# Ethernet.net
KiCad netlist of a schematic drawn in Altium Designer
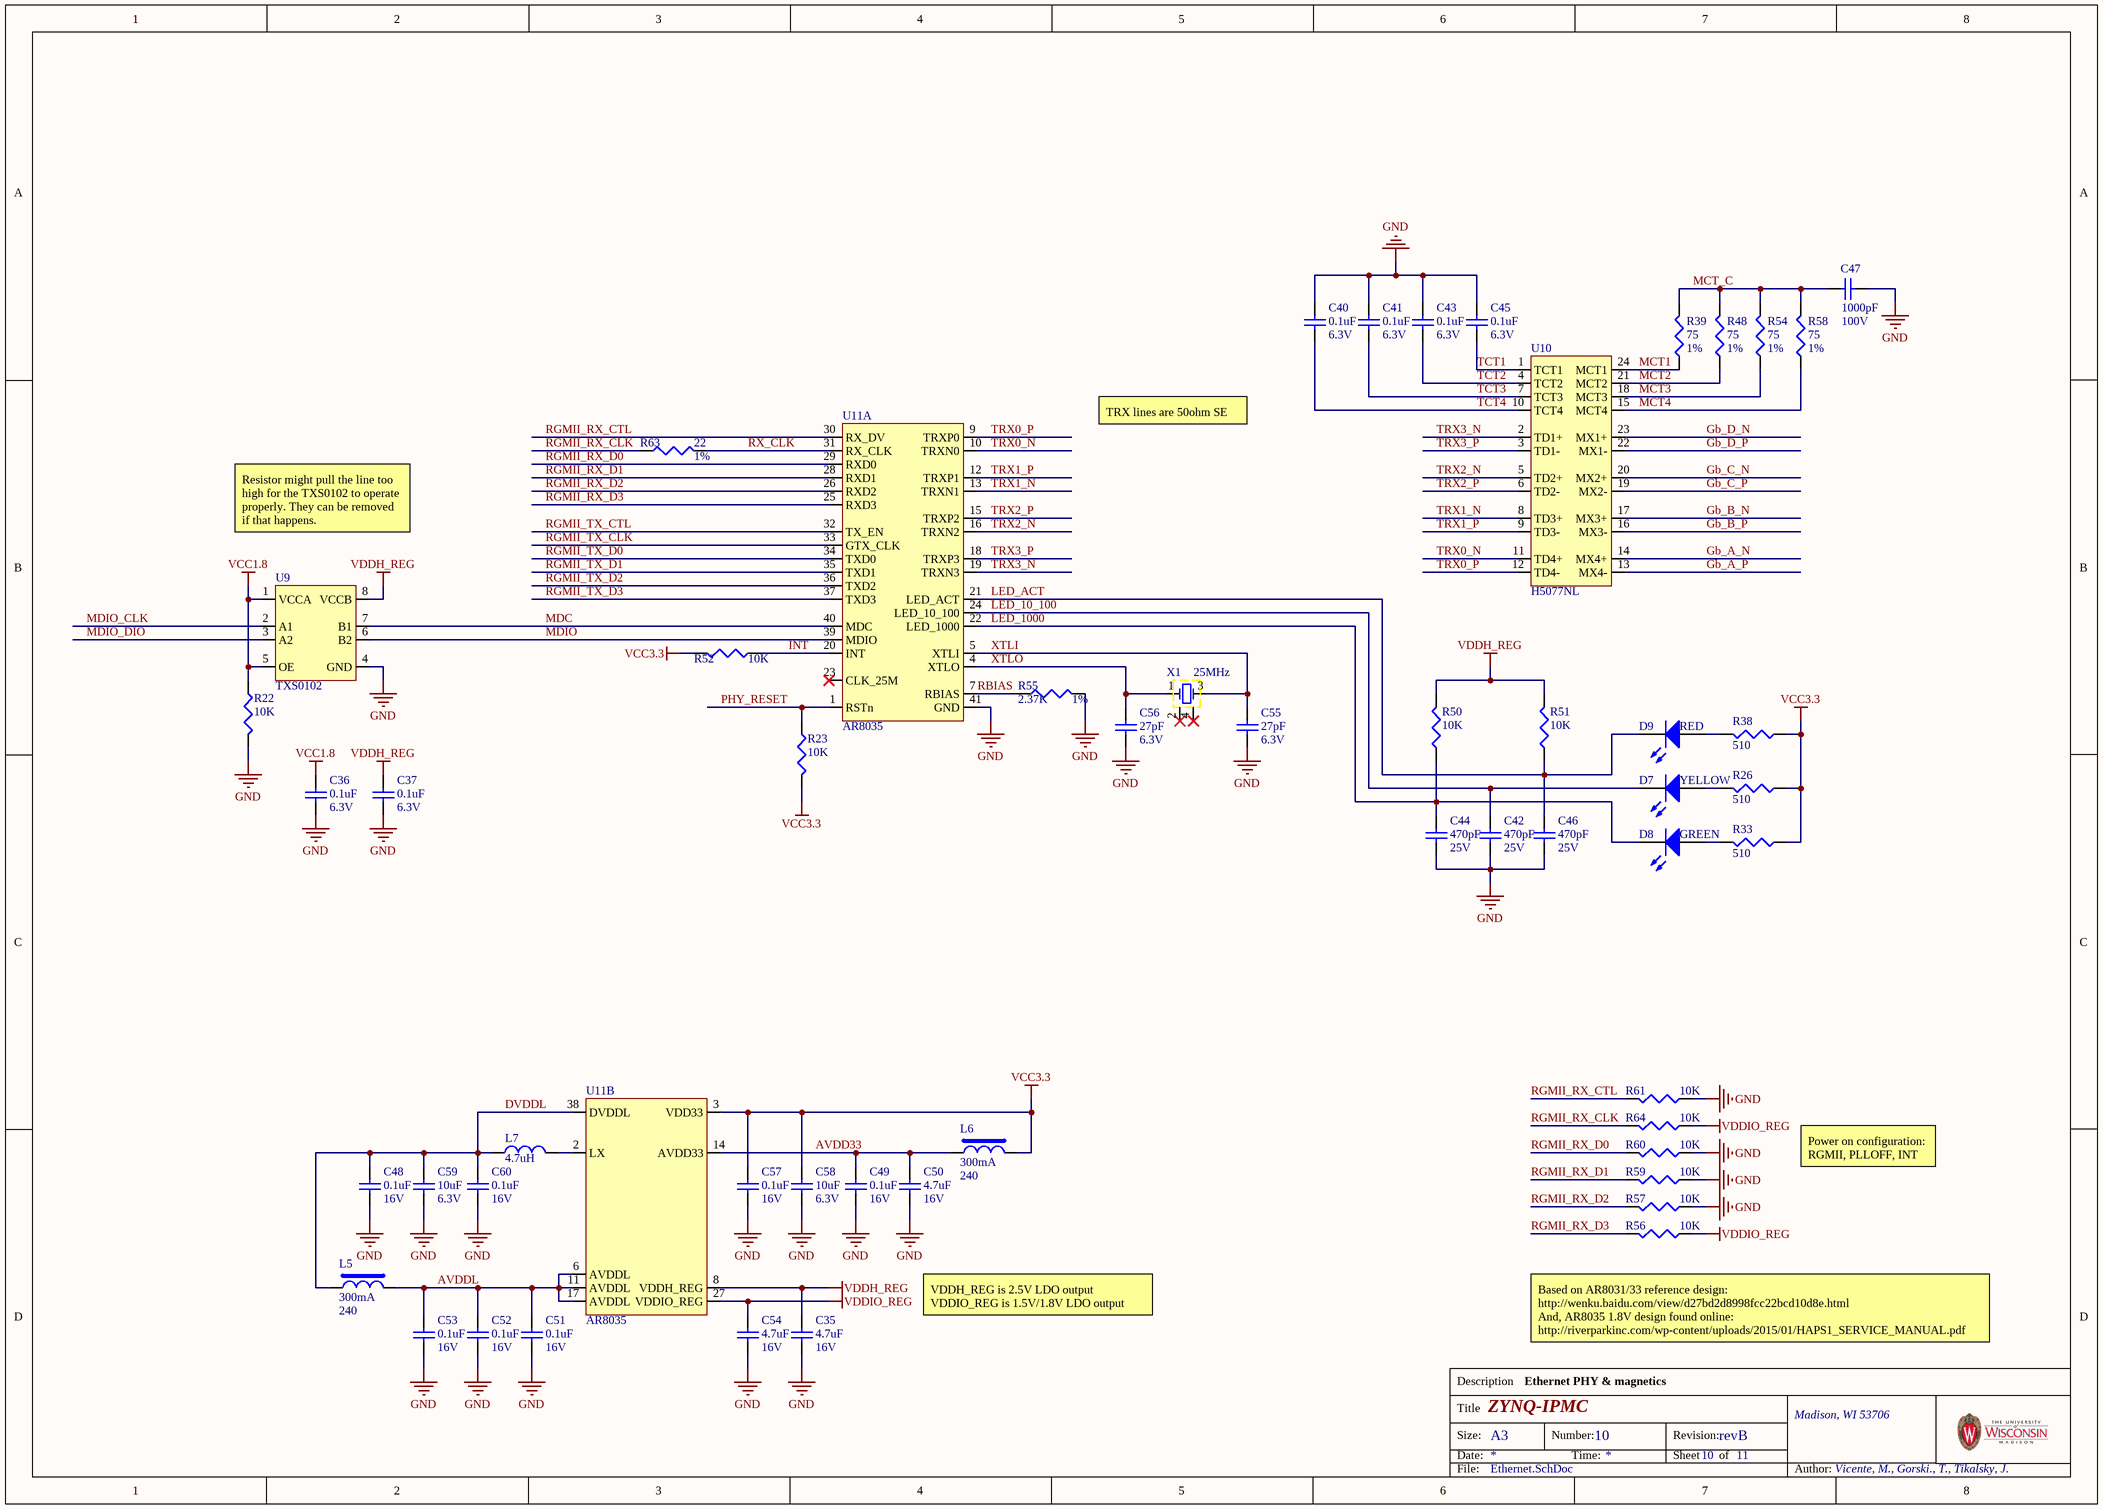
[diagram p0: Ethernet.SchDoc]

(export (version "E")
  (design (tool "Eeschema 10.0.6"))
  (components
    (comp (ref "C35")
      (value "4.7uF")
      (footprint "C0402_IPC_H")
      (description "Capacitor")
      (fields
        (field (name "RATING") "16V")
        (field (name "MANUFACTURER") "AVX")
        (field (name "PART") "0402YD475MAT2A")
      )
      (libsource (lib "CustomParts") (part "Cap"))
    )
    (comp (ref "C36")
      (value "0.1uF")
      (footprint "C0201_IPC_H")
      (description "Capacitor")
      (fields
        (field (name "RATING") "6.3V")
        (field (name "MANUFACTURER") "Murata")
        (field (name "PART") "GRM033R60J104KE19D")
      )
      (libsource (lib "CustomParts") (part "Cap"))
    )
    (comp (ref "C37")
      (value "0.1uF")
      (footprint "C0201_IPC_H")
      (description "Capacitor")
      (fields
        (field (name "RATING") "6.3V")
        (field (name "MANUFACTURER") "Murata")
        (field (name "PART") "GRM033R60J104KE19D")
      )
      (libsource (lib "CustomParts") (part "Cap"))
    )
    (comp (ref "C40")
      (value "0.1uF")
      (footprint "C0201_IPC_H")
      (description "Capacitor")
      (fields
        (field (name "RATING") "6.3V")
        (field (name "MANUFACTURER") "Murata")
        (field (name "PART") "GRM033R60J104KE19D")
      )
      (libsource (lib "CustomParts") (part "Cap"))
    )
    (comp (ref "C41")
      (value "0.1uF")
      (footprint "C0201_IPC_H")
      (description "Capacitor")
      (fields
        (field (name "RATING") "6.3V")
        (field (name "MANUFACTURER") "Murata")
        (field (name "PART") "GRM033R60J104KE19D")
      )
      (libsource (lib "CustomParts") (part "Cap"))
    )
    (comp (ref "C42")
      (value "470pF")
      (footprint "C0201_IPC_H")
      (description "Capacitor")
      (fields
        (field (name "RATING") "25V")
        (field (name "MANUFACTURER") "TDK")
        (field (name "PART") "C0603X7R1E471K030BA")
      )
      (libsource (lib "CustomParts") (part "Cap"))
    )
    (comp (ref "C43")
      (value "0.1uF")
      (footprint "C0201_IPC_H")
      (description "Capacitor")
      (fields
        (field (name "RATING") "6.3V")
        (field (name "MANUFACTURER") "Murata")
        (field (name "PART") "GRM033R60J104KE19D")
      )
      (libsource (lib "CustomParts") (part "Cap"))
    )
    (comp (ref "C44")
      (value "470pF")
      (footprint "C0201_IPC_H")
      (description "Capacitor")
      (fields
        (field (name "RATING") "25V")
        (field (name "MANUFACTURER") "TDK")
        (field (name "PART") "C0603X7R1E471K030BA")
      )
      (libsource (lib "CustomParts") (part "Cap"))
    )
    (comp (ref "C45")
      (value "0.1uF")
      (footprint "C0201_IPC_H")
      (description "Capacitor")
      (fields
        (field (name "RATING") "6.3V")
        (field (name "MANUFACTURER") "Murata")
        (field (name "PART") "GRM033R60J104KE19D")
      )
      (libsource (lib "CustomParts") (part "Cap"))
    )
    (comp (ref "C46")
      (value "470pF")
      (footprint "C0201_IPC_H")
      (description "Capacitor")
      (fields
        (field (name "RATING") "25V")
        (field (name "MANUFACTURER") "TDK")
        (field (name "PART") "C0603X7R1E471K030BA")
      )
      (libsource (lib "CustomParts") (part "Cap"))
    )
    (comp (ref "C47")
      (value "1000pF")
      (footprint "C0402_IPC_H")
      (description "Capacitor")
      (fields
        (field (name "RATING") "100V")
        (field (name "MANUFACTURER") "Murata")
        (field (name "PART") "GRM155R72A102KA01D")
      )
      (libsource (lib "CustomParts") (part "Cap"))
    )
    (comp (ref "C48")
      (value "0.1uF")
      (footprint "C0402_IPC_H")
      (description "Capacitor")
      (fields
        (field (name "RATING") "16V")
        (field (name "MANUFACTURER") "Murata")
        (field (name "PART") "GRM155R71C104KA88D")
      )
      (libsource (lib "CustomParts") (part "Cap"))
    )
    (comp (ref "C49")
      (value "0.1uF")
      (footprint "C0402_IPC_H")
      (description "Capacitor")
      (fields
        (field (name "RATING") "16V")
        (field (name "MANUFACTURER") "Murata")
        (field (name "PART") "GRM155R71C104KA88D")
      )
      (libsource (lib "CustomParts") (part "Cap"))
    )
    (comp (ref "C50")
      (value "4.7uF")
      (footprint "C0402_IPC_H")
      (description "Capacitor")
      (fields
        (field (name "RATING") "16V")
        (field (name "MANUFACTURER") "AVX")
        (field (name "PART") "0402YD475MAT2A")
      )
      (libsource (lib "CustomParts") (part "Cap"))
    )
    (comp (ref "C51")
      (value "0.1uF")
      (footprint "C0402_IPC_H")
      (description "Capacitor")
      (fields
        (field (name "RATING") "16V")
        (field (name "MANUFACTURER") "Murata")
        (field (name "PART") "GRM155R71C104KA88D")
      )
      (libsource (lib "CustomParts") (part "Cap"))
    )
    (comp (ref "C52")
      (value "0.1uF")
      (footprint "C0402_IPC_H")
      (description "Capacitor")
      (fields
        (field (name "RATING") "16V")
        (field (name "MANUFACTURER") "Murata")
        (field (name "PART") "GRM155R71C104KA88D")
      )
      (libsource (lib "CustomParts") (part "Cap"))
    )
    (comp (ref "C53")
      (value "0.1uF")
      (footprint "C0402_IPC_H")
      (description "Capacitor")
      (fields
        (field (name "RATING") "16V")
        (field (name "MANUFACTURER") "Murata")
        (field (name "PART") "GRM155R71C104KA88D")
      )
      (libsource (lib "CustomParts") (part "Cap"))
    )
    (comp (ref "C54")
      (value "4.7uF")
      (footprint "C0402_IPC_H")
      (description "Capacitor")
      (fields
        (field (name "RATING") "16V")
        (field (name "MANUFACTURER") "AVX")
        (field (name "PART") "0402YD475MAT2A")
      )
      (libsource (lib "CustomParts") (part "Cap"))
    )
    (comp (ref "C55")
      (value "27pF")
      (footprint "C0201_IPC_H")
      (description "Capacitor")
      (fields
        (field (name "RATING") "6.3V")
        (field (name "MANUFACTURER") "Murata")
        (field (name "PART") "GJM0335C0J270JB01D")
      )
      (libsource (lib "CustomParts") (part "Cap"))
    )
    (comp (ref "C56")
      (value "27pF")
      (footprint "C0201_IPC_H")
      (description "Capacitor")
      (fields
        (field (name "RATING") "6.3V")
        (field (name "MANUFACTURER") "Murata")
        (field (name "PART") "GJM0335C0J270JB01D")
      )
      (libsource (lib "CustomParts") (part "Cap"))
    )
    (comp (ref "C57")
      (value "0.1uF")
      (footprint "C0402_IPC_H")
      (description "Capacitor")
      (fields
        (field (name "RATING") "16V")
        (field (name "MANUFACTURER") "Murata")
        (field (name "PART") "GRM155R71C104KA88D")
      )
      (libsource (lib "CustomParts") (part "Cap"))
    )
    (comp (ref "C58")
      (value "10uF")
      (footprint "C0402_IPC_H")
      (description "Capacitor")
      (fields
        (field (name "RATING") "6.3V")
        (field (name "MANUFACTURER") "Murata")
        (field (name "PART") "GRM155R60J106ME44D")
      )
      (libsource (lib "CustomParts") (part "Cap"))
    )
    (comp (ref "C59")
      (value "10uF")
      (footprint "C0402_IPC_H")
      (description "Capacitor")
      (fields
        (field (name "RATING") "6.3V")
        (field (name "MANUFACTURER") "Murata")
        (field (name "PART") "GRM155R60J106ME44D")
      )
      (libsource (lib "CustomParts") (part "Cap"))
    )
    (comp (ref "C60")
      (value "0.1uF")
      (footprint "C0402_IPC_H")
      (description "Capacitor")
      (fields
        (field (name "RATING") "16V")
        (field (name "MANUFACTURER") "Murata")
        (field (name "PART") "GRM155R71C104KA88D")
      )
      (libsource (lib "CustomParts") (part "Cap"))
    )
    (comp (ref "D7")
      (value "YELLOW")
      (footprint "LED0603_M")
      (description "Light Emitting Diode")
      (fields (field (name "MANUFACTURER") "Lite-On") (field (name "PART") "LTST-C190KSKT"))
      (libsource (lib "CustomParts") (part "LED"))
    )
    (comp (ref "D8")
      (value "GREEN")
      (footprint "LED0603_M")
      (description "Light Emitting Diode")
      (fields (field (name "MANUFACTURER") "Lite-On") (field (name "PART") "LTST-C190KGKT"))
      (libsource (lib "CustomParts") (part "LED"))
    )
    (comp (ref "D9")
      (value "RED")
      (footprint "LED0603_M")
      (description "Light Emitting Diode")
      (fields (field (name "MANUFACTURER") "Lite-On") (field (name "PART") "LTST-C190KRKT"))
      (libsource (lib "CustomParts") (part "LED"))
    )
    (comp (ref "L5")
      (value "240")
      (footprint "L0402_H")
      (description "Bead Inductor")
      (fields
        (field (name "RATED CURRENT") "300mA")
        (field (name "MANUFACTURER") "Taiyo Yuden")
        (field (name "PART") "BK1005HM241-T")
      )
      (libsource (lib "CustomParts") (part "Bead"))
    )
    (comp (ref "L6")
      (value "240")
      (footprint "L0402_H")
      (description "Bead Inductor")
      (fields
        (field (name "RATED CURRENT") "300mA")
        (field (name "MANUFACTURER") "Taiyo Yuden")
        (field (name "PART") "BK1005HM241-T")
      )
      (libsource (lib "CustomParts") (part "Bead"))
    )
    (comp (ref "L7")
      (value "4.7uH")
      (footprint "L2520_H")
      (description "Inductor")
      (fields (field (name "TOLERANCE") "20%") (field (name "MANUFACTURER") "Wurth"))
      (libsource (lib "CustomParts") (part "Ind"))
    )
    (comp (ref "R22")
      (value "10K")
      (footprint "R0402_IPC_H")
      (description "Resistor")
      (fields (field (name "TOLERANCE") "5%") (field (name "MANUFACTURER") "Panasonic-ECG"))
      (libsource (lib "CustomParts") (part "Res"))
    )
    (comp (ref "R23")
      (value "10K")
      (footprint "R0201_IPC_H")
      (description "Resistor")
      (fields (field (name "TOLERANCE") "1%") (field (name "MANUFACTURER") "Panasonic"))
      (libsource (lib "CustomParts") (part "Res"))
    )
    (comp (ref "R26")
      (value "510")
      (footprint "R0402_IPC_H")
      (description "Resistor")
      (fields (field (name "TOLERANCE") "1%") (field (name "MANUFACTURER") "Panasonic-ECG"))
      (libsource (lib "CustomParts") (part "Res"))
    )
    (comp (ref "R33")
      (value "510")
      (footprint "R0402_IPC_H")
      (description "Resistor")
      (fields (field (name "TOLERANCE") "1%") (field (name "MANUFACTURER") "Panasonic-ECG"))
      (libsource (lib "CustomParts") (part "Res"))
    )
    (comp (ref "R38")
      (value "510")
      (footprint "R0402_IPC_H")
      (description "Resistor")
      (fields (field (name "TOLERANCE") "1%") (field (name "MANUFACTURER") "Panasonic-ECG"))
      (libsource (lib "CustomParts") (part "Res"))
    )
    (comp (ref "R39")
      (value "75")
      (footprint "R0402_IPC_H")
      (description "Resistor")
      (fields
        (field (name "TOLERANCE") "1%")
        (field (name "MANUFACTURER") "Panasonic")
        (field (name "PART") "ERJ-2RKF75R0X")
      )
      (libsource (lib "CustomParts") (part "Res"))
    )
    (comp (ref "R48")
      (value "75")
      (footprint "R0402_IPC_H")
      (description "Resistor")
      (fields
        (field (name "TOLERANCE") "1%")
        (field (name "MANUFACTURER") "Panasonic")
        (field (name "PART") "ERJ-2RKF75R0X")
      )
      (libsource (lib "CustomParts") (part "Res"))
    )
    (comp (ref "R50")
      (value "10K")
      (footprint "R0201_IPC_H")
      (description "Resistor")
      (fields (field (name "TOLERANCE") "1%") (field (name "MANUFACTURER") "Panasonic"))
      (libsource (lib "CustomParts") (part "Res"))
    )
    (comp (ref "R51")
      (value "10K")
      (footprint "R0201_IPC_H")
      (description "Resistor")
      (fields (field (name "TOLERANCE") "1%") (field (name "MANUFACTURER") "Panasonic"))
      (libsource (lib "CustomParts") (part "Res"))
    )
    (comp (ref "R52")
      (value "10K")
      (footprint "R0402_IPC_H")
      (description "Resistor")
      (fields (field (name "TOLERANCE") "5%") (field (name "MANUFACTURER") "Panasonic-ECG"))
      (libsource (lib "CustomParts") (part "Res"))
    )
    (comp (ref "R54")
      (value "75")
      (footprint "R0402_IPC_H")
      (description "Resistor")
      (fields
        (field (name "TOLERANCE") "1%")
        (field (name "MANUFACTURER") "Panasonic")
        (field (name "PART") "ERJ-2RKF75R0X")
      )
      (libsource (lib "CustomParts") (part "Res"))
    )
    (comp (ref "R55")
      (value "2.37K")
      (footprint "R0402_IPC_H")
      (description "Resistor")
      (fields
        (field (name "TOLERANCE") "1%")
        (field (name "MANUFACTURER") "Panasonic")
        (field (name "PART") "ERJ-2RKF2371X")
      )
      (libsource (lib "CustomParts") (part "Res"))
    )
    (comp (ref "R56")
      (value "10K")
      (footprint "R0402_IPC_H")
      (description "Resistor")
      (fields (field (name "TOLERANCE") "5%") (field (name "MANUFACTURER") "Panasonic-ECG"))
      (libsource (lib "CustomParts") (part "Res"))
    )
    (comp (ref "R57")
      (value "10K")
      (footprint "R0402_IPC_H")
      (description "Resistor")
      (fields (field (name "TOLERANCE") "5%") (field (name "MANUFACTURER") "Panasonic-ECG"))
      (libsource (lib "CustomParts") (part "Res"))
    )
    (comp (ref "R58")
      (value "75")
      (footprint "R0402_IPC_H")
      (description "Resistor")
      (fields
        (field (name "TOLERANCE") "1%")
        (field (name "MANUFACTURER") "Panasonic")
        (field (name "PART") "ERJ-2RKF75R0X")
      )
      (libsource (lib "CustomParts") (part "Res"))
    )
    (comp (ref "R59")
      (value "10K")
      (footprint "R0402_IPC_H")
      (description "Resistor")
      (fields (field (name "TOLERANCE") "5%") (field (name "MANUFACTURER") "Panasonic-ECG"))
      (libsource (lib "CustomParts") (part "Res"))
    )
    (comp (ref "R60")
      (value "10K")
      (footprint "R0402_IPC_H")
      (description "Resistor")
      (fields (field (name "TOLERANCE") "5%") (field (name "MANUFACTURER") "Panasonic-ECG"))
      (libsource (lib "CustomParts") (part "Res"))
    )
    (comp (ref "R61")
      (value "10K")
      (footprint "R0402_IPC_H")
      (description "Resistor")
      (fields (field (name "TOLERANCE") "5%") (field (name "MANUFACTURER") "Panasonic-ECG"))
      (libsource (lib "CustomParts") (part "Res"))
    )
    (comp (ref "R63")
      (value "22")
      (footprint "R0201_IPC_H")
      (description "Resistor")
      (fields
        (field (name "TOLERANCE") "1%")
        (field (name "MANUFACTURER") "Panasonic")
        (field (name "PART") "ERJ-1GNF22R0C")
      )
      (libsource (lib "CustomParts") (part "Res"))
    )
    (comp (ref "R64")
      (value "10K")
      (footprint "R0402_IPC_H")
      (description "Resistor")
      (fields (field (name "TOLERANCE") "5%") (field (name "MANUFACTURER") "Panasonic-ECG"))
      (libsource (lib "CustomParts") (part "Res"))
    )
    (comp (ref "U9")
      (value "TXS0102")
      (footprint "X2SON-8_H")
      (description "2-Bit Bidirectional Voltage-Level Translator for Open-Drain and Push-Pull Applications")
      (fields (field (name "MANUFACTURER") "Texas Instruments") (field (name "PART") "TXS0102DQER"))
      (libsource (lib "CustomParts") (part "TXS0102"))
    )
    (comp (ref "U10")
      (value "H5077NL")
      (footprint "H5077NL")
      (description "1000Base-T, Single Port Mini-Magnetics Modules")
      (fields (field (name "MANUFACTURER") "Pulse Electronics"))
      (libsource (lib "CustomParts") (part "H5077NL"))
    )
    (comp (ref "U11")
      (value "AR8035")
      (footprint "QFN40_H")
      (description "Integrated 10/100/1000 Gigabit Ethernet Transceiver")
      (fields (field (name "MANUFACTURER") "Atheros"))
      (libsource (lib "CustomParts") (part "AR8035"))
    )
    (comp (ref "X1")
      (value "25MHz")
      (footprint "XRCGB_F")
      (description "Standard Crystal Oscillator")
      (fields (field (name "MANUFACTURER") "Murata") (field (name "PART") "XRCGB25M000F3M00R0"))
      (libsource (lib "CustomParts") (part "Crystal Osc"))
    )
  )
  (nets
    (net (code "1") (name "/AVDD33") (class "Default")
      (node (ref "C49") (pin "2") (pinfunction "2_2") (pintype "passive"))
      (node (ref "C50") (pin "2") (pinfunction "2_2") (pintype "passive"))
      (node (ref "L6") (pin "1") (pinfunction "1_1") (pintype "passive"))
      (node (ref "U11") (pin "14") (pinfunction "AVDD33_14") (pintype "passive"))
    )
    (net (code "2") (name "/AVDDL") (class "Default")
      (node (ref "C51") (pin "2") (pinfunction "2_2") (pintype "passive"))
      (node (ref "C52") (pin "2") (pinfunction "2_2") (pintype "passive"))
      (node (ref "C53") (pin "2") (pinfunction "2_2") (pintype "passive"))
      (node (ref "L5") (pin "2") (pinfunction "2_2") (pintype "passive"))
      (node (ref "U11") (pin "11") (pinfunction "AVDDL_11") (pintype "passive"))
      (node (ref "U11") (pin "17") (pinfunction "AVDDL_17") (pintype "passive"))
      (node (ref "U11") (pin "6") (pinfunction "AVDDL_6") (pintype "passive"))
    )
    (net (code "3") (name "/DVDDL") (class "Default")
      (node (ref "C48") (pin "2") (pinfunction "2_2") (pintype "passive"))
      (node (ref "C59") (pin "2") (pinfunction "2_2") (pintype "passive"))
      (node (ref "C60") (pin "2") (pinfunction "2_2") (pintype "passive"))
      (node (ref "L5") (pin "1") (pinfunction "1_1") (pintype "passive"))
      (node (ref "L7") (pin "1") (pinfunction "1_1") (pintype "passive"))
      (node (ref "U11") (pin "38") (pinfunction "DVDDL_38") (pintype "passive"))
    )
    (net (code "4") (name "/Gb_A_N") (class "Default")
      (node (ref "U10") (pin "14") (pinfunction "MX4+_14") (pintype "passive"))
    )
    (net (code "5") (name "/Gb_A_P") (class "Default")
      (node (ref "U10") (pin "13") (pinfunction "MX4-_13") (pintype "passive"))
    )
    (net (code "6") (name "/Gb_B_N") (class "Default")
      (node (ref "U10") (pin "17") (pinfunction "MX3+_17") (pintype "passive"))
    )
    (net (code "7") (name "/Gb_B_P") (class "Default")
      (node (ref "U10") (pin "16") (pinfunction "MX3-_16") (pintype "passive"))
    )
    (net (code "8") (name "/Gb_C_N") (class "Default")
      (node (ref "U10") (pin "20") (pinfunction "MX2+_20") (pintype "passive"))
    )
    (net (code "9") (name "/Gb_C_P") (class "Default")
      (node (ref "U10") (pin "19") (pinfunction "MX2-_19") (pintype "passive"))
    )
    (net (code "10") (name "/Gb_D_N") (class "Default")
      (node (ref "U10") (pin "23") (pinfunction "MX1+_23") (pintype "passive"))
    )
    (net (code "11") (name "/Gb_D_P") (class "Default")
      (node (ref "U10") (pin "22") (pinfunction "MX1-_22") (pintype "passive"))
    )
    (net (code "12") (name "/INT") (class "Default")
      (node (ref "R52") (pin "1") (pinfunction "1_1") (pintype "passive"))
      (node (ref "U11") (pin "20") (pinfunction "INT_20") (pintype "passive"))
    )
    (net (code "13") (name "/LED_10_100") (class "Default")
      (node (ref "C42") (pin "2") (pinfunction "2_2") (pintype "passive"))
      (node (ref "D7") (pin "2") (pinfunction "K_2") (pintype "passive"))
      (node (ref "U11") (pin "24") (pinfunction "LED_10_100_24") (pintype "passive"))
    )
    (net (code "14") (name "/LED_1000") (class "Default")
      (node (ref "C44") (pin "2") (pinfunction "2_2") (pintype "passive"))
      (node (ref "D8") (pin "2") (pinfunction "K_2") (pintype "passive"))
      (node (ref "R50") (pin "1") (pinfunction "1_1") (pintype "passive"))
      (node (ref "U11") (pin "22") (pinfunction "LED_1000_22") (pintype "passive"))
    )
    (net (code "15") (name "/LED_ACT") (class "Default")
      (node (ref "C46") (pin "2") (pinfunction "2_2") (pintype "passive"))
      (node (ref "D9") (pin "2") (pinfunction "K_2") (pintype "passive"))
      (node (ref "R51") (pin "1") (pinfunction "1_1") (pintype "passive"))
      (node (ref "U11") (pin "21") (pinfunction "LED_ACT_21") (pintype "passive"))
    )
    (net (code "16") (name "/MCT1") (class "Default")
      (node (ref "R39") (pin "1") (pinfunction "1_1") (pintype "passive"))
      (node (ref "U10") (pin "24") (pinfunction "MCT1_24") (pintype "passive"))
    )
    (net (code "17") (name "/MCT2") (class "Default")
      (node (ref "R48") (pin "1") (pinfunction "1_1") (pintype "passive"))
      (node (ref "U10") (pin "21") (pinfunction "MCT2_21") (pintype "passive"))
    )
    (net (code "18") (name "/MCT3") (class "Default")
      (node (ref "R54") (pin "1") (pinfunction "1_1") (pintype "passive"))
      (node (ref "U10") (pin "18") (pinfunction "MCT3_18") (pintype "passive"))
    )
    (net (code "19") (name "/MCT4") (class "Default")
      (node (ref "R58") (pin "1") (pinfunction "1_1") (pintype "passive"))
      (node (ref "U10") (pin "15") (pinfunction "MCT4_15") (pintype "passive"))
    )
    (net (code "20") (name "/MCT_C") (class "Default")
      (node (ref "C47") (pin "2") (pinfunction "2_2") (pintype "passive"))
      (node (ref "R39") (pin "2") (pinfunction "2_2") (pintype "passive"))
      (node (ref "R48") (pin "2") (pinfunction "2_2") (pintype "passive"))
      (node (ref "R54") (pin "2") (pinfunction "2_2") (pintype "passive"))
      (node (ref "R58") (pin "2") (pinfunction "2_2") (pintype "passive"))
    )
    (net (code "21") (name "/MDC") (class "Default")
      (node (ref "U11") (pin "40") (pinfunction "MDC_40") (pintype "passive"))
      (node (ref "U9") (pin "7") (pinfunction "B1_7") (pintype "passive"))
    )
    (net (code "22") (name "/MDIO") (class "Default")
      (node (ref "U11") (pin "39") (pinfunction "MDIO_39") (pintype "passive"))
      (node (ref "U9") (pin "6") (pinfunction "B2_6") (pintype "passive"))
    )
    (net (code "23") (name "/MDIO_CLK") (class "Default")
      (node (ref "U9") (pin "2") (pinfunction "A1_2") (pintype "passive"))
    )
    (net (code "24") (name "/MDIO_DIO") (class "Default")
      (node (ref "U9") (pin "3") (pinfunction "A2_3") (pintype "passive"))
    )
    (net (code "25") (name "/PHY_RESET") (class "Default")
      (node (ref "R23") (pin "1") (pinfunction "1_1") (pintype "passive"))
      (node (ref "U11") (pin "1") (pinfunction "RSTn_1") (pintype "passive"))
    )
    (net (code "26") (name "/RBIAS") (class "Default")
      (node (ref "R55") (pin "1") (pinfunction "1_1") (pintype "passive"))
      (node (ref "U11") (pin "7") (pinfunction "RBIAS_7") (pintype "passive"))
    )
    (net (code "27") (name "/RGMII_RX_CLK") (class "Default")
      (node (ref "R63") (pin "1") (pinfunction "1_1") (pintype "passive"))
      (node (ref "R64") (pin "2") (pinfunction "2_2") (pintype "passive"))
    )
    (net (code "28") (name "/RGMII_RX_CTL") (class "Default")
      (node (ref "R61") (pin "2") (pinfunction "2_2") (pintype "passive"))
      (node (ref "U11") (pin "30") (pinfunction "RX_DV_30") (pintype "passive"))
    )
    (net (code "29") (name "/RGMII_RX_D0") (class "Default")
      (node (ref "R60") (pin "2") (pinfunction "2_2") (pintype "passive"))
      (node (ref "U11") (pin "29") (pinfunction "RXD0_29") (pintype "passive"))
    )
    (net (code "30") (name "/RGMII_RX_D1") (class "Default")
      (node (ref "R59") (pin "2") (pinfunction "2_2") (pintype "passive"))
      (node (ref "U11") (pin "28") (pinfunction "RXD1_28") (pintype "passive"))
    )
    (net (code "31") (name "/RGMII_RX_D2") (class "Default")
      (node (ref "R57") (pin "2") (pinfunction "2_2") (pintype "passive"))
      (node (ref "U11") (pin "26") (pinfunction "RXD2_26") (pintype "passive"))
    )
    (net (code "32") (name "/RGMII_RX_D3") (class "Default")
      (node (ref "R56") (pin "2") (pinfunction "2_2") (pintype "passive"))
      (node (ref "U11") (pin "25") (pinfunction "RXD3_25") (pintype "passive"))
    )
    (net (code "33") (name "/RGMII_TX_CLK") (class "Default")
      (node (ref "U11") (pin "33") (pinfunction "GTX_CLK_33") (pintype "passive"))
    )
    (net (code "34") (name "/RGMII_TX_CTL") (class "Default")
      (node (ref "U11") (pin "32") (pinfunction "TX_EN_32") (pintype "passive"))
    )
    (net (code "35") (name "/RGMII_TX_D0") (class "Default")
      (node (ref "U11") (pin "34") (pinfunction "TXD0_34") (pintype "passive"))
    )
    (net (code "36") (name "/RGMII_TX_D1") (class "Default")
      (node (ref "U11") (pin "35") (pinfunction "TXD1_35") (pintype "passive"))
    )
    (net (code "37") (name "/RGMII_TX_D2") (class "Default")
      (node (ref "U11") (pin "36") (pinfunction "TXD2_36") (pintype "passive"))
    )
    (net (code "38") (name "/RGMII_TX_D3") (class "Default")
      (node (ref "U11") (pin "37") (pinfunction "TXD3_37") (pintype "passive"))
    )
    (net (code "39") (name "/RX_CLK") (class "Default")
      (node (ref "R63") (pin "2") (pinfunction "2_2") (pintype "passive"))
      (node (ref "U11") (pin "31") (pinfunction "RX_CLK_31") (pintype "passive"))
    )
    (net (code "40") (name "/TCT1") (class "Default")
      (node (ref "C45") (pin "1") (pinfunction "1_1") (pintype "passive"))
      (node (ref "U10") (pin "1") (pinfunction "TCT1_1") (pintype "passive"))
    )
    (net (code "41") (name "/TCT2") (class "Default")
      (node (ref "C43") (pin "1") (pinfunction "1_1") (pintype "passive"))
      (node (ref "U10") (pin "4") (pinfunction "TCT2_4") (pintype "passive"))
    )
    (net (code "42") (name "/TCT3") (class "Default")
      (node (ref "C41") (pin "1") (pinfunction "1_1") (pintype "passive"))
      (node (ref "U10") (pin "7") (pinfunction "TCT3_7") (pintype "passive"))
    )
    (net (code "43") (name "/TCT4") (class "Default")
      (node (ref "C40") (pin "1") (pinfunction "1_1") (pintype "passive"))
      (node (ref "U10") (pin "10") (pinfunction "TCT4_10") (pintype "passive"))
    )
    (net (code "44") (name "/TRX0_N") (class "Default")
      (node (ref "U10") (pin "11") (pinfunction "TD4+_11") (pintype "passive"))
      (node (ref "U11") (pin "10") (pinfunction "TRXN0_10") (pintype "passive"))
    )
    (net (code "45") (name "/TRX0_P") (class "Default")
      (node (ref "U10") (pin "12") (pinfunction "TD4-_12") (pintype "passive"))
      (node (ref "U11") (pin "9") (pinfunction "TRXP0_9") (pintype "passive"))
    )
    (net (code "46") (name "/TRX1_N") (class "Default")
      (node (ref "U10") (pin "8") (pinfunction "TD3+_8") (pintype "passive"))
      (node (ref "U11") (pin "13") (pinfunction "TRXN1_13") (pintype "passive"))
    )
    (net (code "47") (name "/TRX1_P") (class "Default")
      (node (ref "U10") (pin "9") (pinfunction "TD3-_9") (pintype "passive"))
      (node (ref "U11") (pin "12") (pinfunction "TRXP1_12") (pintype "passive"))
    )
    (net (code "48") (name "/TRX2_N") (class "Default")
      (node (ref "U10") (pin "5") (pinfunction "TD2+_5") (pintype "passive"))
      (node (ref "U11") (pin "16") (pinfunction "TRXN2_16") (pintype "passive"))
    )
    (net (code "49") (name "/TRX2_P") (class "Default")
      (node (ref "U10") (pin "6") (pinfunction "TD2-_6") (pintype "passive"))
      (node (ref "U11") (pin "15") (pinfunction "TRXP2_15") (pintype "passive"))
    )
    (net (code "50") (name "/TRX3_N") (class "Default")
      (node (ref "U10") (pin "2") (pinfunction "TD1+_2") (pintype "passive"))
      (node (ref "U11") (pin "19") (pinfunction "TRXN3_19") (pintype "passive"))
    )
    (net (code "51") (name "/TRX3_P") (class "Default")
      (node (ref "U10") (pin "3") (pinfunction "TD1-_3") (pintype "passive"))
      (node (ref "U11") (pin "18") (pinfunction "TRXP3_18") (pintype "passive"))
    )
    (net (code "52") (name "/XTLI") (class "Default")
      (node (ref "C55") (pin "2") (pinfunction "2_2") (pintype "passive"))
      (node (ref "U11") (pin "5") (pinfunction "XTLI_5") (pintype "passive"))
      (node (ref "X1") (pin "3") (pinfunction "3_3") (pintype "passive"))
    )
    (net (code "53") (name "/XTLO") (class "Default")
      (node (ref "C56") (pin "2") (pinfunction "2_2") (pintype "passive"))
      (node (ref "U11") (pin "4") (pinfunction "XTLO_4") (pintype "passive"))
      (node (ref "X1") (pin "1") (pinfunction "1_1") (pintype "passive"))
    )
    (net (code "54") (name "GND") (class "Default")
      (node (ref "C35") (pin "1") (pinfunction "1_1") (pintype "passive"))
      (node (ref "C36") (pin "1") (pinfunction "1_1") (pintype "passive"))
      (node (ref "C37") (pin "1") (pinfunction "1_1") (pintype "passive"))
      (node (ref "C40") (pin "2") (pinfunction "2_2") (pintype "passive"))
      (node (ref "C41") (pin "2") (pinfunction "2_2") (pintype "passive"))
      (node (ref "C42") (pin "1") (pinfunction "1_1") (pintype "passive"))
      (node (ref "C43") (pin "2") (pinfunction "2_2") (pintype "passive"))
      (node (ref "C44") (pin "1") (pinfunction "1_1") (pintype "passive"))
      (node (ref "C45") (pin "2") (pinfunction "2_2") (pintype "passive"))
      (node (ref "C46") (pin "1") (pinfunction "1_1") (pintype "passive"))
      (node (ref "C47") (pin "1") (pinfunction "1_1") (pintype "passive"))
      (node (ref "C48") (pin "1") (pinfunction "1_1") (pintype "passive"))
      (node (ref "C49") (pin "1") (pinfunction "1_1") (pintype "passive"))
      (node (ref "C50") (pin "1") (pinfunction "1_1") (pintype "passive"))
      (node (ref "C51") (pin "1") (pinfunction "1_1") (pintype "passive"))
      (node (ref "C52") (pin "1") (pinfunction "1_1") (pintype "passive"))
      (node (ref "C53") (pin "1") (pinfunction "1_1") (pintype "passive"))
      (node (ref "C54") (pin "1") (pinfunction "1_1") (pintype "passive"))
      (node (ref "C55") (pin "1") (pinfunction "1_1") (pintype "passive"))
      (node (ref "C56") (pin "1") (pinfunction "1_1") (pintype "passive"))
      (node (ref "C57") (pin "1") (pinfunction "1_1") (pintype "passive"))
      (node (ref "C58") (pin "1") (pinfunction "1_1") (pintype "passive"))
      (node (ref "C59") (pin "1") (pinfunction "1_1") (pintype "passive"))
      (node (ref "C60") (pin "1") (pinfunction "1_1") (pintype "passive"))
      (node (ref "R22") (pin "2") (pinfunction "2_2") (pintype "passive"))
      (node (ref "R55") (pin "2") (pinfunction "2_2") (pintype "passive"))
      (node (ref "R57") (pin "1") (pinfunction "1_1") (pintype "passive"))
      (node (ref "R59") (pin "1") (pinfunction "1_1") (pintype "passive"))
      (node (ref "R60") (pin "1") (pinfunction "1_1") (pintype "passive"))
      (node (ref "R61") (pin "1") (pinfunction "1_1") (pintype "passive"))
      (node (ref "U11") (pin "41") (pinfunction "GND_41") (pintype "passive"))
      (node (ref "U9") (pin "4") (pinfunction "GND_4") (pintype "passive"))
    )
    (net (code "55") (name "Net-(D7-A)") (class "Default")
      (node (ref "D7") (pin "1") (pinfunction "A_1") (pintype "passive"))
      (node (ref "R26") (pin "2") (pinfunction "2_2") (pintype "passive"))
    )
    (net (code "56") (name "Net-(D8-A)") (class "Default")
      (node (ref "D8") (pin "1") (pinfunction "A_1") (pintype "passive"))
      (node (ref "R33") (pin "2") (pinfunction "2_2") (pintype "passive"))
    )
    (net (code "57") (name "Net-(D9-A)") (class "Default")
      (node (ref "D9") (pin "1") (pinfunction "A_1") (pintype "passive"))
      (node (ref "R38") (pin "2") (pinfunction "2_2") (pintype "passive"))
    )
    (net (code "58") (name "Net-(U11B-LX)") (class "Default")
      (node (ref "L7") (pin "2") (pinfunction "2_2") (pintype "passive"))
      (node (ref "U11") (pin "2") (pinfunction "LX_2") (pintype "passive"))
    )
    (net (code "59") (name "VCC1.8") (class "Default")
      (node (ref "C36") (pin "2") (pinfunction "2_2") (pintype "passive"))
      (node (ref "R22") (pin "1") (pinfunction "1_1") (pintype "passive"))
      (node (ref "U9") (pin "1") (pinfunction "VCCA_1") (pintype "passive"))
      (node (ref "U9") (pin "5") (pinfunction "OE_5") (pintype "passive"))
    )
    (net (code "60") (name "VCC3.3") (class "Default")
      (node (ref "C57") (pin "2") (pinfunction "2_2") (pintype "passive"))
      (node (ref "C58") (pin "2") (pinfunction "2_2") (pintype "passive"))
      (node (ref "L6") (pin "2") (pinfunction "2_2") (pintype "passive"))
      (node (ref "R23") (pin "2") (pinfunction "2_2") (pintype "passive"))
      (node (ref "R26") (pin "1") (pinfunction "1_1") (pintype "passive"))
      (node (ref "R33") (pin "1") (pinfunction "1_1") (pintype "passive"))
      (node (ref "R38") (pin "1") (pinfunction "1_1") (pintype "passive"))
      (node (ref "R52") (pin "2") (pinfunction "2_2") (pintype "passive"))
      (node (ref "U11") (pin "3") (pinfunction "VDD33_3") (pintype "passive"))
    )
    (net (code "61") (name "VDDH_REG") (class "Default")
      (node (ref "C35") (pin "2") (pinfunction "2_2") (pintype "passive"))
      (node (ref "C37") (pin "2") (pinfunction "2_2") (pintype "passive"))
      (node (ref "R50") (pin "2") (pinfunction "2_2") (pintype "passive"))
      (node (ref "R51") (pin "2") (pinfunction "2_2") (pintype "passive"))
      (node (ref "U11") (pin "8") (pinfunction "VDDH_REG_8") (pintype "passive"))
      (node (ref "U9") (pin "8") (pinfunction "VCCB_8") (pintype "passive"))
    )
    (net (code "62") (name "VDDIO_REG") (class "Default")
      (node (ref "C54") (pin "2") (pinfunction "2_2") (pintype "passive"))
      (node (ref "R56") (pin "1") (pinfunction "1_1") (pintype "passive"))
      (node (ref "R64") (pin "1") (pinfunction "1_1") (pintype "passive"))
      (node (ref "U11") (pin "27") (pinfunction "VDDIO_REG_27") (pintype "passive"))
    )
    (net (code "63") (name "unconnected-(U11A-CLK_25M-Pad23)") (class "Default")
      (node (ref "U11") (pin "23") (pinfunction "CLK_25M_23") (pintype "passive+no_connect"))
    )
    (net (code "64") (name "unconnected-(X1-Pad2)") (class "Default")
      (node (ref "X1") (pin "2") (pinfunction "2_2") (pintype "passive+no_connect"))
    )
    (net (code "65") (name "unconnected-(X1-Pad4)") (class "Default")
      (node (ref "X1") (pin "4") (pinfunction "4_4") (pintype "passive+no_connect"))
    )
  )
)
